# battery_powered_sensor.net
KiCad netlist of a schematic drawn in EAGLE
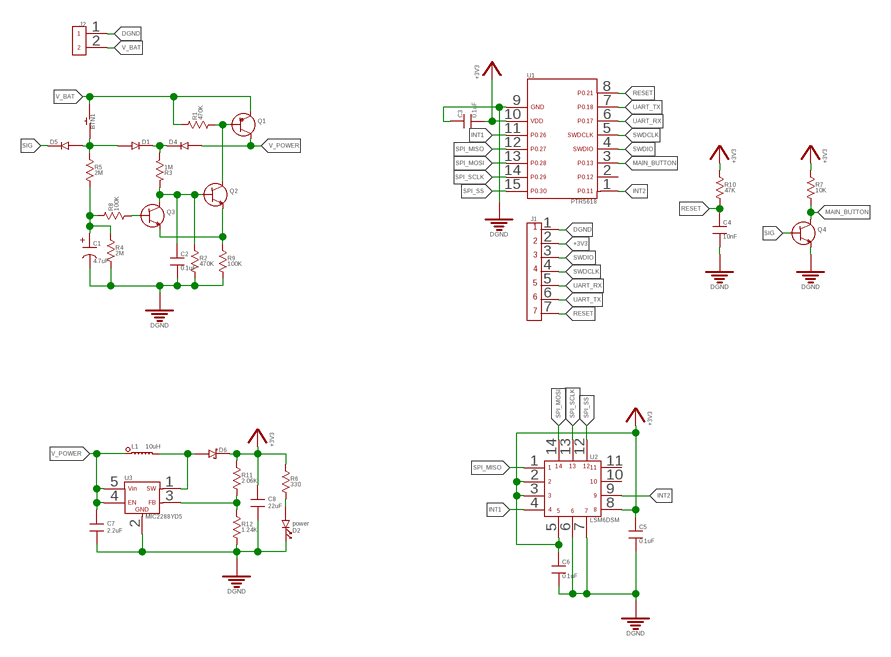
[diagram p0: schematic, sheet 1]

(export (version "E")
  (design (tool "Eeschema 10.0.6"))
  (components
    (comp (ref "BTN1")
      (value "BTN_NORMAL_OFF_6_3.5_SMD")
      (footprint "eagle-import:BTN_6_3.5_SMD")
      (libsource (lib "eagle-import") (part "BTN_NORMAL_OFF_6_3.5_SMD"))
    )
    (comp (ref "C1")
      (value "4.7uF")
      (footprint "eagle-import:CAP_530_530")
      (libsource (lib "eagle-import") (part "CAPACITOR_POLARIZED_530_530"))
    )
    (comp (ref "C2")
      (value "0.1uF")
      (footprint "eagle-import:0805")
      (libsource (lib "eagle-import") (part "CAPACITOR_FIXED_0805"))
    )
    (comp (ref "C3")
      (value "0.1uF")
      (footprint "eagle-import:0805")
      (libsource (lib "eagle-import") (part "CAPACITOR_FIXED_0805"))
    )
    (comp (ref "C4")
      (value "10nF")
      (footprint "eagle-import:0805")
      (libsource (lib "eagle-import") (part "CAPACITOR_FIXED_0805"))
    )
    (comp (ref "C5")
      (value "0.1uF")
      (footprint "eagle-import:0805")
      (libsource (lib "eagle-import") (part "CAPACITOR_FIXED_0805"))
    )
    (comp (ref "C6")
      (value "0.1uF")
      (footprint "eagle-import:0805")
      (libsource (lib "eagle-import") (part "CAPACITOR_FIXED_0805"))
    )
    (comp (ref "C7")
      (value "2.2uF")
      (footprint "eagle-import:0805")
      (libsource (lib "eagle-import") (part "CAPACITOR_FIXED_0805"))
    )
    (comp (ref "C8")
      (value "22uF")
      (footprint "eagle-import:0805")
      (libsource (lib "eagle-import") (part "CAPACITOR_FIXED_0805"))
    )
    (comp (ref "D1")
      (value "DIODE0805")
      (footprint "eagle-import:0805DIODE")
      (libsource (lib "eagle-import") (part "DIODE0805"))
    )
    (comp (ref "D2")
      (value "power")
      (footprint "eagle-import:0805DIODE")
      (libsource (lib "eagle-import") (part "LED-0805"))
    )
    (comp (ref "D4")
      (value "DIODE0805")
      (footprint "eagle-import:0805DIODE")
      (libsource (lib "eagle-import") (part "DIODE0805"))
    )
    (comp (ref "D5")
      (value "DIODE0805")
      (footprint "eagle-import:0805DIODE")
      (libsource (lib "eagle-import") (part "DIODE0805"))
    )
    (comp (ref "D6")
      (value "SCHOTTKY_DIODE_0805")
      (footprint "eagle-import:0805DIODE")
      (libsource (lib "eagle-import") (part "SCHOTTKY_DIODE_0805"))
    )
    (comp (ref "J1")
      (value "7PIN_HEADER_PITCH2.54MM_TH")
      (footprint "eagle-import:7PIN_HEADER_PITCH2.54MM_TH")
      (libsource (lib "eagle-import") (part "7PIN_HEADER_PITCH2.54MM_TH"))
    )
    (comp (ref "J2")
      (value "2PIN_HEADER_PITCH2.54MM_TH")
      (footprint "eagle-import:2PIN_HEADER_PITCH2.54MM_TH")
      (libsource (lib "eagle-import") (part "2PIN_HEADER_PITCH2.54MM_TH"))
    )
    (comp (ref "L1")
      (value "10uH")
      (footprint "eagle-import:1008")
      (libsource (lib "eagle-import") (part "INDUCTOR_1008"))
    )
    (comp (ref "Q1")
      (value "MMBT4403")
      (footprint "eagle-import:SOT_23_3")
      (libsource (lib "eagle-import") (part "MMBT4403"))
    )
    (comp (ref "Q2")
      (value "BC846")
      (footprint "eagle-import:SOT_23_3")
      (libsource (lib "eagle-import") (part "BC846"))
    )
    (comp (ref "Q3")
      (value "BC846")
      (footprint "eagle-import:SOT_23_3")
      (libsource (lib "eagle-import") (part "BC846"))
    )
    (comp (ref "Q4")
      (value "BC846")
      (footprint "eagle-import:SOT_23_3")
      (libsource (lib "eagle-import") (part "BC846"))
    )
    (comp (ref "R1")
      (value "470K")
      (footprint "eagle-import:0805")
      (libsource (lib "eagle-import") (part "RESISTOR_0805"))
    )
    (comp (ref "R2")
      (value "470K")
      (footprint "eagle-import:0805")
      (libsource (lib "eagle-import") (part "RESISTOR_0805"))
    )
    (comp (ref "R3")
      (value "1M")
      (footprint "eagle-import:0805")
      (libsource (lib "eagle-import") (part "RESISTOR_0805"))
    )
    (comp (ref "R4")
      (value "2M")
      (footprint "eagle-import:0805")
      (libsource (lib "eagle-import") (part "RESISTOR_0805"))
    )
    (comp (ref "R5")
      (value "2M")
      (footprint "eagle-import:0805")
      (libsource (lib "eagle-import") (part "RESISTOR_0805"))
    )
    (comp (ref "R6")
      (value "330")
      (footprint "eagle-import:0805")
      (libsource (lib "eagle-import") (part "RESISTOR_0805"))
    )
    (comp (ref "R7")
      (value "10K")
      (footprint "eagle-import:0805")
      (libsource (lib "eagle-import") (part "RESISTOR_0805"))
    )
    (comp (ref "R8")
      (value "100K")
      (footprint "eagle-import:0805")
      (libsource (lib "eagle-import") (part "RESISTOR_0805"))
    )
    (comp (ref "R9")
      (value "100K")
      (footprint "eagle-import:0805")
      (libsource (lib "eagle-import") (part "RESISTOR_0805"))
    )
    (comp (ref "R10")
      (value "47K")
      (footprint "eagle-import:0805")
      (libsource (lib "eagle-import") (part "RESISTOR_0805"))
    )
    (comp (ref "R11")
      (value "2.06K")
      (footprint "eagle-import:0805")
      (libsource (lib "eagle-import") (part "RESISTOR_0805"))
    )
    (comp (ref "R12")
      (value "1.24K")
      (footprint "eagle-import:0805")
      (libsource (lib "eagle-import") (part "RESISTOR_0805"))
    )
    (comp (ref "U1")
      (value "PTR5618")
      (footprint "eagle-import:PTR5618")
      (libsource (lib "eagle-import") (part "PTR5618"))
    )
    (comp (ref "U2")
      (value "LSM6DSM")
      (footprint "eagle-import:LGA-14L")
      (libsource (lib "eagle-import") (part "LSM6DSM"))
    )
    (comp (ref "U3")
      (value "MIC2288YD5")
      (footprint "eagle-import:SOT-23-5")
      (libsource (lib "eagle-import") (part "MIC2288YD5"))
    )
  )
  (nets
    (net (code "1") (name "+3V3") (class "Default")
      (node (ref "C3") (pin "2") (pinfunction "2_2") (pintype "passive"))
      (node (ref "C5") (pin "1") (pinfunction "1_1") (pintype "passive"))
      (node (ref "C6") (pin "1") (pinfunction "1_1") (pintype "passive"))
      (node (ref "C8") (pin "1") (pinfunction "1_1") (pintype "passive"))
      (node (ref "D6") (pin "1") (pinfunction "1_1") (pintype "passive"))
      (node (ref "J1") (pin "2") (pinfunction "2_2") (pintype "passive"))
      (node (ref "R10") (pin "1") (pinfunction "1_1") (pintype "passive"))
      (node (ref "R11") (pin "1") (pinfunction "1_1") (pintype "passive"))
      (node (ref "R6") (pin "1") (pinfunction "1_1") (pintype "passive"))
      (node (ref "R7") (pin "1") (pinfunction "1_1") (pintype "passive"))
      (node (ref "U1") (pin "10") (pinfunction "10_10") (pintype "passive"))
      (node (ref "U2") (pin "2") (pinfunction "2_2") (pintype "passive"))
      (node (ref "U2") (pin "3") (pinfunction "3_3") (pintype "passive"))
      (node (ref "U2") (pin "5") (pinfunction "5_5") (pintype "passive"))
      (node (ref "U2") (pin "8") (pinfunction "8_8") (pintype "passive"))
    )
    (net (code "2") (name "DGND") (class "Default")
      (node (ref "C1") (pin "2") (pinfunction "2_2") (pintype "passive"))
      (node (ref "C2") (pin "2") (pinfunction "2_2") (pintype "passive"))
      (node (ref "C3") (pin "1") (pinfunction "1_1") (pintype "passive"))
      (node (ref "C4") (pin "2") (pinfunction "2_2") (pintype "passive"))
      (node (ref "C5") (pin "2") (pinfunction "2_2") (pintype "passive"))
      (node (ref "C6") (pin "2") (pinfunction "2_2") (pintype "passive"))
      (node (ref "C7") (pin "2") (pinfunction "2_2") (pintype "passive"))
      (node (ref "C8") (pin "2") (pinfunction "2_2") (pintype "passive"))
      (node (ref "D2") (pin "1") (pinfunction "K_1") (pintype "passive"))
      (node (ref "J1") (pin "1") (pinfunction "1_1") (pintype "passive"))
      (node (ref "J2") (pin "1") (pinfunction "1_1") (pintype "passive"))
      (node (ref "Q4") (pin "3") (pinfunction "E_3") (pintype "passive"))
      (node (ref "R12") (pin "2") (pinfunction "2_2") (pintype "passive"))
      (node (ref "R2") (pin "2") (pinfunction "2_2") (pintype "passive"))
      (node (ref "R4") (pin "2") (pinfunction "2_2") (pintype "passive"))
      (node (ref "R9") (pin "2") (pinfunction "2_2") (pintype "passive"))
      (node (ref "U1") (pin "9") (pinfunction "9_9") (pintype "passive"))
      (node (ref "U2") (pin "6") (pinfunction "6_6") (pintype "passive"))
      (node (ref "U2") (pin "7") (pinfunction "7_7") (pintype "passive"))
      (node (ref "U3") (pin "2") (pinfunction "GND_2") (pintype "passive"))
    )
    (net (code "3") (name "INT1") (class "Default")
      (node (ref "U1") (pin "11") (pinfunction "11_11") (pintype "passive"))
      (node (ref "U2") (pin "4") (pinfunction "4_4") (pintype "passive"))
    )
    (net (code "4") (name "INT2") (class "Default")
      (node (ref "U1") (pin "1") (pinfunction "1_1") (pintype "passive"))
      (node (ref "U2") (pin "9") (pinfunction "9_9") (pintype "passive"))
    )
    (net (code "5") (name "MAIN_BUTTON") (class "Default")
      (node (ref "Q4") (pin "2") (pinfunction "C_2") (pintype "passive"))
      (node (ref "R7") (pin "2") (pinfunction "2_2") (pintype "passive"))
      (node (ref "U1") (pin "3") (pinfunction "3_3") (pintype "passive"))
    )
    (net (code "6") (name "Net-(BTN1-Pad1)") (class "Default")
      (node (ref "BTN1") (pin "1") (pinfunction "1_1") (pintype "passive"))
      (node (ref "D1") (pin "2") (pinfunction "2_2") (pintype "passive"))
      (node (ref "D5") (pin "2") (pinfunction "2_2") (pintype "passive"))
      (node (ref "R5") (pin "1") (pinfunction "1_1") (pintype "passive"))
    )
    (net (code "7") (name "Net-(C1-Pad1)") (class "Default")
      (node (ref "C1") (pin "1") (pinfunction "1_1") (pintype "passive"))
      (node (ref "R4") (pin "1") (pinfunction "1_1") (pintype "passive"))
      (node (ref "R5") (pin "2") (pinfunction "2_2") (pintype "passive"))
      (node (ref "R8") (pin "1") (pinfunction "1_1") (pintype "passive"))
    )
    (net (code "8") (name "Net-(D1-Pad1)") (class "Default")
      (node (ref "D1") (pin "1") (pinfunction "1_1") (pintype "passive"))
      (node (ref "D4") (pin "1") (pinfunction "1_1") (pintype "passive"))
      (node (ref "R3") (pin "2") (pinfunction "2_2") (pintype "passive"))
    )
    (net (code "9") (name "Net-(D2-A)") (class "Default")
      (node (ref "D2") (pin "2") (pinfunction "A_2") (pintype "passive"))
      (node (ref "R6") (pin "2") (pinfunction "2_2") (pintype "passive"))
    )
    (net (code "10") (name "Net-(Q1-B)") (class "Default")
      (node (ref "Q1") (pin "1") (pinfunction "B_1") (pintype "passive"))
      (node (ref "Q2") (pin "2") (pinfunction "C_2") (pintype "passive"))
      (node (ref "R1") (pin "2") (pinfunction "2_2") (pintype "passive"))
    )
    (net (code "11") (name "Net-(Q2-B)") (class "Default")
      (node (ref "C2") (pin "1") (pinfunction "1_1") (pintype "passive"))
      (node (ref "Q2") (pin "1") (pinfunction "B_1") (pintype "passive"))
      (node (ref "Q3") (pin "2") (pinfunction "C_2") (pintype "passive"))
      (node (ref "R2") (pin "1") (pinfunction "1_1") (pintype "passive"))
      (node (ref "R3") (pin "1") (pinfunction "1_1") (pintype "passive"))
    )
    (net (code "12") (name "Net-(Q2-E)") (class "Default")
      (node (ref "Q2") (pin "3") (pinfunction "E_3") (pintype "passive"))
      (node (ref "Q3") (pin "3") (pinfunction "E_3") (pintype "passive"))
      (node (ref "R9") (pin "1") (pinfunction "1_1") (pintype "passive"))
    )
    (net (code "13") (name "Net-(Q3-B)") (class "Default")
      (node (ref "Q3") (pin "1") (pinfunction "B_1") (pintype "passive"))
      (node (ref "R8") (pin "2") (pinfunction "2_2") (pintype "passive"))
    )
    (net (code "14") (name "Net-(U3-FB)") (class "Default")
      (node (ref "R11") (pin "2") (pinfunction "2_2") (pintype "passive"))
      (node (ref "R12") (pin "1") (pinfunction "1_1") (pintype "passive"))
      (node (ref "U3") (pin "3") (pinfunction "FB_3") (pintype "passive"))
    )
    (net (code "15") (name "Net-(U3-SW)") (class "Default")
      (node (ref "D6") (pin "2") (pinfunction "2_2") (pintype "passive"))
      (node (ref "L1") (pin "2") (pinfunction "2_2") (pintype "passive"))
      (node (ref "U3") (pin "1") (pinfunction "SW_1") (pintype "passive"))
    )
    (net (code "16") (name "RESET") (class "Default")
      (node (ref "C4") (pin "1") (pinfunction "1_1") (pintype "passive"))
      (node (ref "J1") (pin "7") (pinfunction "7_7") (pintype "passive"))
      (node (ref "R10") (pin "2") (pinfunction "2_2") (pintype "passive"))
      (node (ref "U1") (pin "8") (pinfunction "8_8") (pintype "passive"))
    )
    (net (code "17") (name "SIG") (class "Default")
      (node (ref "D5") (pin "1") (pinfunction "1_1") (pintype "passive"))
      (node (ref "Q4") (pin "1") (pinfunction "B_1") (pintype "passive"))
    )
    (net (code "18") (name "SPI_MISO") (class "Default")
      (node (ref "U1") (pin "12") (pinfunction "12_12") (pintype "passive"))
      (node (ref "U2") (pin "1") (pinfunction "1_1") (pintype "passive"))
    )
    (net (code "19") (name "SPI_MOSI") (class "Default")
      (node (ref "U1") (pin "13") (pinfunction "13_13") (pintype "passive"))
      (node (ref "U2") (pin "14") (pinfunction "14_14") (pintype "passive"))
    )
    (net (code "20") (name "SPI_SCLK") (class "Default")
      (node (ref "U1") (pin "14") (pinfunction "14_14") (pintype "passive"))
      (node (ref "U2") (pin "13") (pinfunction "13_13") (pintype "passive"))
    )
    (net (code "21") (name "SPI_SS") (class "Default")
      (node (ref "U1") (pin "15") (pinfunction "15_15") (pintype "passive"))
      (node (ref "U2") (pin "12") (pinfunction "12_12") (pintype "passive"))
    )
    (net (code "22") (name "SWDCLK") (class "Default")
      (node (ref "J1") (pin "4") (pinfunction "4_4") (pintype "passive"))
      (node (ref "U1") (pin "5") (pinfunction "5_5") (pintype "passive"))
    )
    (net (code "23") (name "SWDIO") (class "Default")
      (node (ref "J1") (pin "3") (pinfunction "3_3") (pintype "passive"))
      (node (ref "U1") (pin "4") (pinfunction "4_4") (pintype "passive"))
    )
    (net (code "24") (name "UART_RX") (class "Default")
      (node (ref "J1") (pin "5") (pinfunction "5_5") (pintype "passive"))
      (node (ref "U1") (pin "6") (pinfunction "6_6") (pintype "passive"))
    )
    (net (code "25") (name "UART_TX") (class "Default")
      (node (ref "J1") (pin "6") (pinfunction "6_6") (pintype "passive"))
      (node (ref "U1") (pin "7") (pinfunction "7_7") (pintype "passive"))
    )
    (net (code "26") (name "V_BAT") (class "Default")
      (node (ref "BTN1") (pin "2") (pinfunction "2_2") (pintype "passive"))
      (node (ref "J2") (pin "2") (pinfunction "2_2") (pintype "passive"))
      (node (ref "Q1") (pin "3") (pinfunction "E_3") (pintype "passive"))
      (node (ref "R1") (pin "1") (pinfunction "1_1") (pintype "passive"))
    )
    (net (code "27") (name "V_POWER") (class "Default")
      (node (ref "C7") (pin "1") (pinfunction "1_1") (pintype "passive"))
      (node (ref "D4") (pin "2") (pinfunction "2_2") (pintype "passive"))
      (node (ref "L1") (pin "1") (pinfunction "1_1") (pintype "passive"))
      (node (ref "Q1") (pin "2") (pinfunction "C_2") (pintype "passive"))
      (node (ref "U3") (pin "4") (pinfunction "EN_4") (pintype "passive"))
      (node (ref "U3") (pin "5") (pinfunction "VIN_5") (pintype "passive"))
    )
    (net (code "28") (name "unconnected-(U1-Pad2)") (class "Default")
      (node (ref "U1") (pin "2") (pinfunction "2_2") (pintype "passive"))
    )
    (net (code "29") (name "unconnected-(U2-Pad10)") (class "Default")
      (node (ref "U2") (pin "10") (pinfunction "10_10") (pintype "passive"))
    )
    (net (code "30") (name "unconnected-(U2-Pad11)") (class "Default")
      (node (ref "U2") (pin "11") (pinfunction "11_11") (pintype "passive"))
    )
  )
)
